# ETH1G_RGMII_RTL8211F.net
KiCad netlist of a schematic drawn in Altium Designer
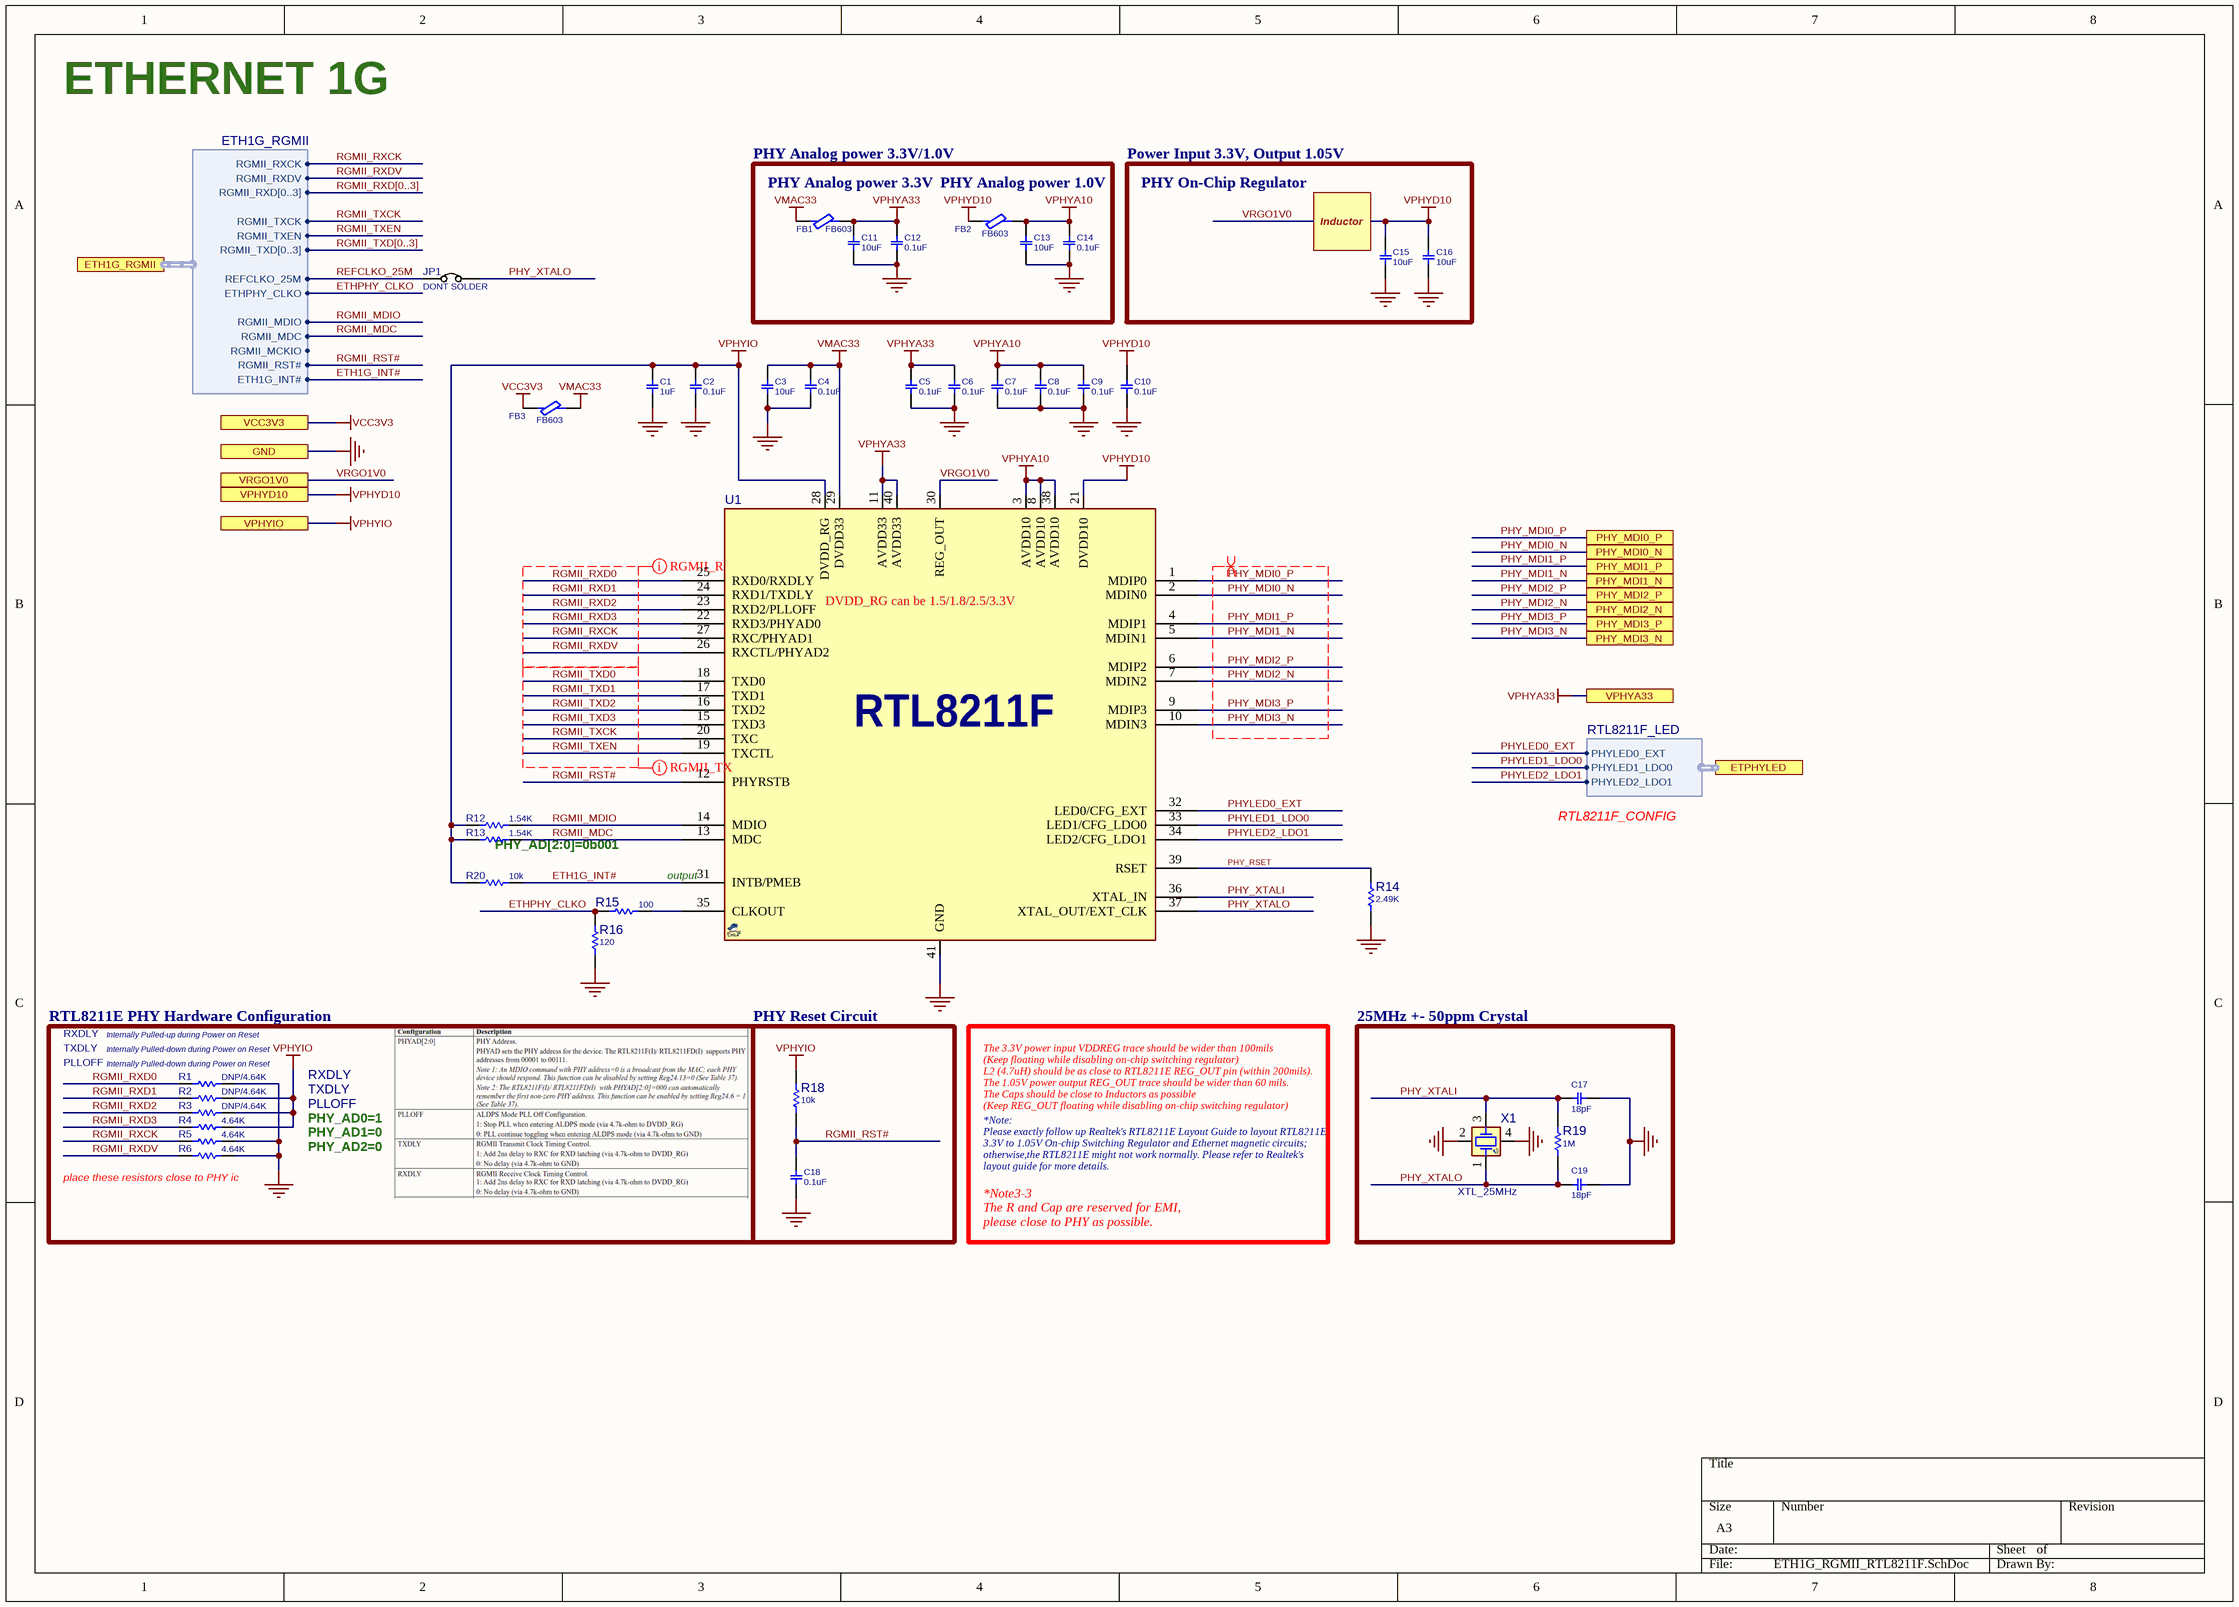
[diagram p0: ETH1G_RGMII_RTL8211F.SchDoc]

(export (version "E")
  (design (tool "Eeschema 10.0.6"))
  (components
    (comp (ref "C1")
      (value "1uF")
      (footprint "C0402")
      (description "CAP, MLCC")
      (fields (field (name "MANF_P#") "CL05A105KO5NNND") (field (name "MANF") "Samsung"))
      (libsource (lib "passive_smd") (part "CAP_SMD_MLCC"))
    )
    (comp (ref "C2")
      (value "0.1uF")
      (footprint "C0402")
      (description "CAP, MLCC")
      (fields (field (name "MANF_P#") "GRM155R61E104") (field (name "MANF") "Murata"))
      (libsource (lib "mlcc_smd_passive") (part "CAP_SMD_MLCC_100n50T"))
    )
    (comp (ref "C3")
      (value "10uF")
      (footprint "C0402")
      (description "CAP, MLCC")
      (fields (field (name "MANF_P#") "CL05A106MP5NUNC") (field (name "MANF") "Samsung"))
      (libsource (lib "mlcc_smd_passive") (part "CAP_SMD_MLCC_100n50T"))
    )
    (comp (ref "C4")
      (value "0.1uF")
      (footprint "C0402")
      (description "CAP, MLCC")
      (fields (field (name "MANF_P#") "GRM155R61E104") (field (name "MANF") "Murata"))
      (libsource (lib "mlcc_smd_passive") (part "CAP_SMD_MLCC_100n50T"))
    )
    (comp (ref "C5")
      (value "0.1uF")
      (footprint "C0402")
      (description "CAP, MLCC")
      (fields (field (name "MANF_P#") "GRM155R61E104") (field (name "MANF") "Murata"))
      (libsource (lib "mlcc_smd_passive") (part "CAP_SMD_MLCC_100n50T"))
    )
    (comp (ref "C6")
      (value "0.1uF")
      (footprint "C0402")
      (description "CAP, MLCC")
      (fields (field (name "MANF_P#") "GRM155R61E104") (field (name "MANF") "Murata"))
      (libsource (lib "mlcc_smd_passive") (part "CAP_SMD_MLCC_100n50T"))
    )
    (comp (ref "C7")
      (value "0.1uF")
      (footprint "C0402")
      (description "CAP, MLCC")
      (fields (field (name "MANF_P#") "GRM155R61E104") (field (name "MANF") "Murata"))
      (libsource (lib "mlcc_smd_passive") (part "CAP_SMD_MLCC_100n50T"))
    )
    (comp (ref "C8")
      (value "0.1uF")
      (footprint "C0402")
      (description "CAP, MLCC")
      (fields (field (name "MANF_P#") "GRM155R61E104") (field (name "MANF") "Murata"))
      (libsource (lib "mlcc_smd_passive") (part "CAP_SMD_MLCC_100n50T"))
    )
    (comp (ref "C9")
      (value "0.1uF")
      (footprint "C0402")
      (description "CAP, MLCC")
      (fields (field (name "MANF_P#") "GRM155R61E104") (field (name "MANF") "Murata"))
      (libsource (lib "mlcc_smd_passive") (part "CAP_SMD_MLCC_100n50T"))
    )
    (comp (ref "C10")
      (value "0.1uF")
      (footprint "C0402")
      (description "CAP, MLCC")
      (fields (field (name "MANF_P#") "GRM155R61E104") (field (name "MANF") "Murata"))
      (libsource (lib "mlcc_smd_passive") (part "CAP_SMD_MLCC_100n50T"))
    )
    (comp (ref "C11")
      (value "10uF")
      (footprint "C0402")
      (description "CAP, MLCC")
      (fields (field (name "MANF_P#") "CL05A106MP5NUNC") (field (name "MANF") "Samsung"))
      (libsource (lib "mlcc_smd_passive") (part "CAP_SMD_MLCC_100n50T"))
    )
    (comp (ref "C12")
      (value "0.1uF")
      (footprint "C0402")
      (description "CAP, MLCC")
      (fields (field (name "MANF_P#") "GRM155R61E104") (field (name "MANF") "Murata"))
      (libsource (lib "mlcc_smd_passive") (part "CAP_SMD_MLCC_100n50T"))
    )
    (comp (ref "C13")
      (value "10uF")
      (footprint "C0402")
      (description "CAP, MLCC")
      (fields (field (name "MANF_P#") "CL05A106MP5NUNC") (field (name "MANF") "Samsung"))
      (libsource (lib "mlcc_smd_passive") (part "CAP_SMD_MLCC_100n50T"))
    )
    (comp (ref "C14")
      (value "0.1uF")
      (footprint "C0402")
      (description "CAP, MLCC")
      (fields (field (name "MANF_P#") "GRM155R61E104") (field (name "MANF") "Murata"))
      (libsource (lib "mlcc_smd_passive") (part "CAP_SMD_MLCC_100n50T"))
    )
    (comp (ref "C15")
      (value "10uF")
      (footprint "C0402")
      (description "CAP, MLCC")
      (fields (field (name "MANF_P#") "CL05A106MP5NUNC") (field (name "MANF") "Samsung"))
      (libsource (lib "mlcc_smd_passive") (part "CAP_SMD_MLCC_100n50T"))
    )
    (comp (ref "C16")
      (value "10uF")
      (footprint "C0402")
      (description "CAP, MLCC")
      (fields (field (name "MANF_P#") "CL05A106MP5NUNC") (field (name "MANF") "Samsung"))
      (libsource (lib "mlcc_smd_passive") (part "CAP_SMD_MLCC_100n50T"))
    )
    (comp (ref "C17")
      (value "18pF")
      (footprint "C0402A")
      (description "CAP, MLCC")
      (fields (field (name "MANF_P#") "CC0402JRNPO9BN180") (field (name "MANF") "Yageo"))
      (libsource (lib "mlcc_smd_passive") (part "CAP_SMD_MLCC_100n50T"))
    )
    (comp (ref "C18")
      (value "0.1uF")
      (footprint "C0402")
      (description "CAP, MLCC")
      (fields (field (name "MANF_P#") "GRM155R61E104") (field (name "MANF") "Murata"))
      (libsource (lib "mlcc_smd_passive") (part "CAP_SMD_MLCC_100n50T"))
    )
    (comp (ref "C19")
      (value "18pF")
      (footprint "C0402A")
      (description "CAP, MLCC")
      (fields (field (name "MANF_P#") "CC0402JRNPO9BN180") (field (name "MANF") "Yageo"))
      (libsource (lib "mlcc_smd_passive") (part "CAP_SMD_MLCC_100n50T"))
    )
    (comp (ref "FB1")
      (value "FB603")
      (footprint "L0603")
      (description "FERRITE_Bead, 0603, 0.8A, 300mOhm, 1000@100MHz")
      (fields (field (name "MANF") "MURATA") (field (name "MANF_P#") "BLM18KG601SN1D"))
      (libsource (lib "emi_filter") (part "FBEAD_SMD_MPZ1608S102"))
    )
    (comp (ref "FB2")
      (value "FB603")
      (footprint "L0603")
      (description "FERRITE_Bead, 0603, 0.8A, 300mOhm, 1000@100MHz")
      (fields (field (name "MANF") "MURATA") (field (name "MANF_P#") "BLM18KG601SN1D"))
      (libsource (lib "emi_filter") (part "FBEAD_SMD_MPZ1608S102"))
    )
    (comp (ref "FB3")
      (value "FB603")
      (footprint "L0603")
      (description "FERRITE_Bead, 0603, 0.8A, 300mOhm, 1000@100MHz")
      (fields (field (name "MANF") "MURATA") (field (name "MANF_P#") "BLM18KG601SN1D"))
      (libsource (lib "emi_filter") (part "FBEAD_SMD_MPZ1608S102"))
    )
    (comp (ref "JP1")
      (value "DONT SOLDER")
      (footprint "JP_40X50")
      (description "JUMPER,  solder")
      (fields (field (name "MANF") "MANF") (field (name "MANF_P#") "MANF_P#"))
      (libsource (lib "test-tp_jumper") (part "JUMPER_SOLDER"))
    )
    (comp (ref "R1")
      (value "DNP/4.64K")
      (footprint "R0402")
      (description "RESISTOR, SMD")
      (libsource (lib "passive_res_smd") (part "RES_SMD_10K_0402"))
    )
    (comp (ref "R2")
      (value "DNP/4.64K")
      (footprint "R0402")
      (description "RESISTOR, SMD")
      (libsource (lib "passive_res_smd") (part "RES_SMD_10K_0402"))
    )
    (comp (ref "R3")
      (value "DNP/4.64K")
      (footprint "R0402")
      (description "RESISTOR, SMD")
      (libsource (lib "passive_res_smd") (part "RES_SMD_10K_0402"))
    )
    (comp (ref "R4")
      (value "4.64K")
      (footprint "R0402")
      (description "RESISTOR, SMD")
      (libsource (lib "passive_res_smd") (part "RES_SMD_10K_0402"))
    )
    (comp (ref "R5")
      (value "4.64K")
      (footprint "R0402")
      (description "RESISTOR, SMD")
      (libsource (lib "passive_res_smd") (part "RES_SMD_10K_0402"))
    )
    (comp (ref "R6")
      (value "4.64K")
      (footprint "R0402")
      (description "RESISTOR, SMD")
      (libsource (lib "passive_res_smd") (part "RES_SMD_10K_0402"))
    )
    (comp (ref "R12")
      (value "1.54K")
      (footprint "R0402")
      (description "RESISTOR, SMD")
      (libsource (lib "passive_res_smd") (part "RES_SMD_10K_0402"))
    )
    (comp (ref "R13")
      (value "1.54K")
      (footprint "R0402")
      (description "RESISTOR, SMD")
      (libsource (lib "passive_res_smd") (part "RES_SMD_10K_0402"))
    )
    (comp (ref "R14")
      (value "2.49K")
      (footprint "R0402")
      (description "RESISTOR, SMD")
      (libsource (lib "passive_res_smd") (part "RES_SMD_10K_0402"))
    )
    (comp (ref "R15")
      (value "100")
      (footprint "R0402")
      (description "RESISTOR, SMD")
      (libsource (lib "passive_res_smd") (part "RES_SMD_10K_0402"))
    )
    (comp (ref "R16")
      (value "120")
      (footprint "R0402")
      (description "RESISTOR, SMD")
      (libsource (lib "passive_res_smd") (part "RES_SMD_10K_0402"))
    )
    (comp (ref "R18")
      (value "10k")
      (footprint "R0402")
      (description "RESISTOR, SMD")
      (libsource (lib "passive_res_smd") (part "RES_SMD_10K_0402"))
    )
    (comp (ref "R19")
      (value "1M")
      (footprint "R0402")
      (description "RESISTOR, SMD")
      (libsource (lib "passive_res_smd") (part "RES_SMD_10K_0402"))
    )
    (comp (ref "R20")
      (value "10k")
      (footprint "R0402")
      (description "RESISTOR, SMD")
      (libsource (lib "passive_res_smd") (part "RES_SMD_10K_0402"))
    )
    (comp (ref "U1")
      (value "RTL8211F")
      (footprint "QFN40_40T")
      (description "Ethernet Transceiver, 10/100/1000, RGMII")
      (fields (field (name "MANF_P#") "RTL8211FI-CG") (field (name "MANF") "Realtek"))
      (libsource (lib "ethernet") (part "RTL8211F_QFN40"))
    )
    (comp (ref "X1")
      (value "XTL_25MHz")
      (footprint "XTL_4_2016")
      (description "CRYSTAL 25.00 MHZ 6pF, 10PPM")
      (fields (field (name "MANF") "Murata") (field (name "MANF_P#") "XRCGB25M000F1H00R0"))
      (libsource (lib "crystal") (part "XTL_4_25MHz_3225"))
    )
  )
  (nets
    (net (code "3") (name "/ETH1G_INT#") (class "Default")
      (node (ref "R20") (pin "2") (pinfunction "2_2") (pintype "passive"))
      (node (ref "U1") (pin "31") (pinfunction "INTB/PMEB_31") (pintype "passive"))
    )
    (net (code "5") (name "/ETHPHY_CLKO") (class "Default")
      (node (ref "R15") (pin "1") (pinfunction "1_1") (pintype "passive"))
      (node (ref "R16") (pin "2") (pinfunction "2_2") (pintype "passive"))
    )
    (net (code "6") (name "/PHYLED0_EXT") (class "Default")
      (node (ref "U1") (pin "32") (pinfunction "LED0/CFG_EXT_32") (pintype "passive"))
    )
    (net (code "7") (name "/PHYLED1_LDO0") (class "Default")
      (node (ref "U1") (pin "33") (pinfunction "LED1/CFG_LDO0_33") (pintype "passive"))
    )
    (net (code "8") (name "/PHYLED2_LDO1") (class "Default")
      (node (ref "U1") (pin "34") (pinfunction "LED2/CFG_LDO1_34") (pintype "passive"))
    )
    (net (code "9") (name "/PHY_MDI0_N") (class "Default")
      (node (ref "U1") (pin "2") (pinfunction "MDIN0_2") (pintype "passive"))
    )
    (net (code "10") (name "/PHY_MDI0_P") (class "Default")
      (node (ref "U1") (pin "1") (pinfunction "MDIP0_1") (pintype "passive"))
    )
    (net (code "11") (name "/PHY_MDI1_N") (class "Default")
      (node (ref "U1") (pin "5") (pinfunction "MDIN1_5") (pintype "passive"))
    )
    (net (code "12") (name "/PHY_MDI1_P") (class "Default")
      (node (ref "U1") (pin "4") (pinfunction "MDIP1_4") (pintype "passive"))
    )
    (net (code "13") (name "/PHY_MDI2_N") (class "Default")
      (node (ref "U1") (pin "7") (pinfunction "MDIN2_7") (pintype "passive"))
    )
    (net (code "14") (name "/PHY_MDI2_P") (class "Default")
      (node (ref "U1") (pin "6") (pinfunction "MDIP2_6") (pintype "passive"))
    )
    (net (code "15") (name "/PHY_MDI3_N") (class "Default")
      (node (ref "U1") (pin "10") (pinfunction "MDIN3_10") (pintype "passive"))
    )
    (net (code "16") (name "/PHY_MDI3_P") (class "Default")
      (node (ref "U1") (pin "9") (pinfunction "MDIP3_9") (pintype "passive"))
    )
    (net (code "17") (name "/PHY_RSET") (class "Default")
      (node (ref "R14") (pin "2") (pinfunction "2_2") (pintype "passive"))
      (node (ref "U1") (pin "39") (pinfunction "RSET_39") (pintype "passive"))
    )
    (net (code "18") (name "/PHY_XTALI") (class "Default")
      (node (ref "C17") (pin "1") (pinfunction "1_1") (pintype "passive"))
      (node (ref "R19") (pin "2") (pinfunction "2_2") (pintype "passive"))
      (node (ref "U1") (pin "36") (pinfunction "XTAL_IN_36") (pintype "passive"))
      (node (ref "X1") (pin "3") (pinfunction "XB_3") (pintype "passive"))
    )
    (net (code "19") (name "/PHY_XTALO") (class "Default")
      (node (ref "C19") (pin "1") (pinfunction "1_1") (pintype "passive"))
      (node (ref "JP1") (pin "2") (pinfunction "2_2") (pintype "passive"))
      (node (ref "R19") (pin "1") (pinfunction "1_1") (pintype "passive"))
      (node (ref "U1") (pin "37") (pinfunction "XTAL_OUT/EXT_CLK_37") (pintype "passive"))
      (node (ref "X1") (pin "1") (pinfunction "XA_1") (pintype "passive"))
    )
    (net (code "20") (name "/REFCLKO_25M") (class "Default")
      (node (ref "JP1") (pin "1") (pinfunction "1_1") (pintype "passive"))
    )
    (net (code "21") (name "/RGMII_MDC") (class "Default")
      (node (ref "R13") (pin "2") (pinfunction "2_2") (pintype "passive"))
      (node (ref "U1") (pin "13") (pinfunction "MDC_13") (pintype "passive"))
    )
    (net (code "22") (name "/RGMII_MDIO") (class "Default")
      (node (ref "R12") (pin "2") (pinfunction "2_2") (pintype "passive"))
      (node (ref "U1") (pin "14") (pinfunction "MDIO_14") (pintype "passive"))
    )
    (net (code "23") (name "/RGMII_RST#") (class "Default")
      (node (ref "C18") (pin "2") (pinfunction "2_2") (pintype "passive"))
      (node (ref "R18") (pin "2") (pinfunction "2_2") (pintype "passive"))
      (node (ref "U1") (pin "12") (pinfunction "PHYRSTB_12") (pintype "passive"))
    )
    (net (code "24") (name "/RGMII_RXCK") (class "Default")
      (node (ref "R5") (pin "1") (pinfunction "1_1") (pintype "passive"))
      (node (ref "U1") (pin "27") (pinfunction "RXC/PHYAD1_27") (pintype "passive"))
    )
    (net (code "25") (name "/RGMII_RXD0") (class "Default")
      (node (ref "R1") (pin "1") (pinfunction "1_1") (pintype "passive"))
      (node (ref "U1") (pin "25") (pinfunction "RXD0/RXDLY_25") (pintype "passive"))
    )
    (net (code "26") (name "/RGMII_RXD1") (class "Default")
      (node (ref "R2") (pin "1") (pinfunction "1_1") (pintype "passive"))
      (node (ref "U1") (pin "24") (pinfunction "RXD1/TXDLY_24") (pintype "passive"))
    )
    (net (code "27") (name "/RGMII_RXD2") (class "Default")
      (node (ref "R3") (pin "1") (pinfunction "1_1") (pintype "passive"))
      (node (ref "U1") (pin "23") (pinfunction "RXD2/PLLOFF_23") (pintype "passive"))
    )
    (net (code "28") (name "/RGMII_RXD3") (class "Default")
      (node (ref "R4") (pin "1") (pinfunction "1_1") (pintype "passive"))
      (node (ref "U1") (pin "22") (pinfunction "RXD3/PHYAD0_22") (pintype "passive"))
    )
    (net (code "29") (name "/RGMII_RXDV") (class "Default")
      (node (ref "R6") (pin "1") (pinfunction "1_1") (pintype "passive"))
      (node (ref "U1") (pin "26") (pinfunction "RXCTL/PHYAD2_26") (pintype "passive"))
    )
    (net (code "30") (name "/RGMII_TXCK") (class "Default")
      (node (ref "U1") (pin "20") (pinfunction "TXC_20") (pintype "passive"))
    )
    (net (code "31") (name "/RGMII_TXD0") (class "Default")
      (node (ref "U1") (pin "18") (pinfunction "TXD0_18") (pintype "passive"))
    )
    (net (code "32") (name "/RGMII_TXD1") (class "Default")
      (node (ref "U1") (pin "17") (pinfunction "TXD1_17") (pintype "passive"))
    )
    (net (code "33") (name "/RGMII_TXD2") (class "Default")
      (node (ref "U1") (pin "16") (pinfunction "TXD2_16") (pintype "passive"))
    )
    (net (code "34") (name "/RGMII_TXD3") (class "Default")
      (node (ref "U1") (pin "15") (pinfunction "TXD3_15") (pintype "passive"))
    )
    (net (code "36") (name "/RGMII_TXEN") (class "Default")
      (node (ref "U1") (pin "19") (pinfunction "TXCTL_19") (pintype "passive"))
    )
    (net (code "37") (name "/VRGO1V0") (class "Default")
      (node (ref "U1") (pin "30") (pinfunction "REG_OUT_30") (pintype "passive"))
    )
    (net (code "40") (name "GND") (class "Default")
      (node (ref "C1") (pin "1") (pinfunction "1_1") (pintype "passive"))
      (node (ref "C10") (pin "2") (pinfunction "2_2") (pintype "passive"))
      (node (ref "C11") (pin "2") (pinfunction "2_2") (pintype "passive"))
      (node (ref "C12") (pin "2") (pinfunction "2_2") (pintype "passive"))
      (node (ref "C13") (pin "2") (pinfunction "2_2") (pintype "passive"))
      (node (ref "C14") (pin "2") (pinfunction "2_2") (pintype "passive"))
      (node (ref "C15") (pin "2") (pinfunction "2_2") (pintype "passive"))
      (node (ref "C16") (pin "2") (pinfunction "2_2") (pintype "passive"))
      (node (ref "C17") (pin "2") (pinfunction "2_2") (pintype "passive"))
      (node (ref "C18") (pin "1") (pinfunction "1_1") (pintype "passive"))
      (node (ref "C19") (pin "2") (pinfunction "2_2") (pintype "passive"))
      (node (ref "C2") (pin "2") (pinfunction "2_2") (pintype "passive"))
      (node (ref "C3") (pin "2") (pinfunction "2_2") (pintype "passive"))
      (node (ref "C4") (pin "2") (pinfunction "2_2") (pintype "passive"))
      (node (ref "C5") (pin "2") (pinfunction "2_2") (pintype "passive"))
      (node (ref "C6") (pin "2") (pinfunction "2_2") (pintype "passive"))
      (node (ref "C7") (pin "2") (pinfunction "2_2") (pintype "passive"))
      (node (ref "C8") (pin "2") (pinfunction "2_2") (pintype "passive"))
      (node (ref "C9") (pin "2") (pinfunction "2_2") (pintype "passive"))
      (node (ref "R1") (pin "2") (pinfunction "2_2") (pintype "passive"))
      (node (ref "R14") (pin "1") (pinfunction "1_1") (pintype "passive"))
      (node (ref "R16") (pin "1") (pinfunction "1_1") (pintype "passive"))
      (node (ref "R5") (pin "2") (pinfunction "2_2") (pintype "passive"))
      (node (ref "R6") (pin "2") (pinfunction "2_2") (pintype "passive"))
      (node (ref "U1") (pin "41") (pinfunction "GND_41") (pintype "passive"))
      (node (ref "X1") (pin "2") (pinfunction "GND1_2") (pintype "passive"))
      (node (ref "X1") (pin "4") (pinfunction "GND2_4") (pintype "passive"))
    )
    (net (code "41") (name "Net-(U1-CLKOUT)") (class "Default")
      (node (ref "R15") (pin "2") (pinfunction "2_2") (pintype "passive"))
      (node (ref "U1") (pin "35") (pinfunction "CLKOUT_35") (pintype "passive"))
    )
    (net (code "42") (name "VCC3V3") (class "Default")
      (node (ref "FB3") (pin "1") (pinfunction "1_1") (pintype "passive"))
    )
    (net (code "43") (name "VMAC33") (class "Default")
      (node (ref "C3") (pin "1") (pinfunction "1_1") (pintype "passive"))
      (node (ref "C4") (pin "1") (pinfunction "1_1") (pintype "passive"))
      (node (ref "FB1") (pin "1") (pinfunction "1_1") (pintype "passive"))
      (node (ref "FB3") (pin "2") (pinfunction "2_2") (pintype "passive"))
      (node (ref "U1") (pin "29") (pinfunction "DVDD33_29") (pintype "passive"))
    )
    (net (code "44") (name "VPHYA10") (class "Default")
      (node (ref "C13") (pin "1") (pinfunction "1_1") (pintype "passive"))
      (node (ref "C14") (pin "1") (pinfunction "1_1") (pintype "passive"))
      (node (ref "C7") (pin "1") (pinfunction "1_1") (pintype "passive"))
      (node (ref "C8") (pin "1") (pinfunction "1_1") (pintype "passive"))
      (node (ref "C9") (pin "1") (pinfunction "1_1") (pintype "passive"))
      (node (ref "FB2") (pin "2") (pinfunction "2_2") (pintype "passive"))
      (node (ref "U1") (pin "3") (pinfunction "AVDD10_3") (pintype "passive"))
      (node (ref "U1") (pin "38") (pinfunction "AVDD10_38") (pintype "passive"))
      (node (ref "U1") (pin "8") (pinfunction "AVDD10_8") (pintype "passive"))
    )
    (net (code "45") (name "VPHYA33") (class "Default")
      (node (ref "C11") (pin "1") (pinfunction "1_1") (pintype "passive"))
      (node (ref "C12") (pin "1") (pinfunction "1_1") (pintype "passive"))
      (node (ref "C5") (pin "1") (pinfunction "1_1") (pintype "passive"))
      (node (ref "C6") (pin "1") (pinfunction "1_1") (pintype "passive"))
      (node (ref "FB1") (pin "2") (pinfunction "2_2") (pintype "passive"))
      (node (ref "U1") (pin "11") (pinfunction "AVDD33_11") (pintype "passive"))
      (node (ref "U1") (pin "40") (pinfunction "AVDD33_40") (pintype "passive"))
    )
    (net (code "46") (name "VPHYD10") (class "Default")
      (node (ref "C10") (pin "1") (pinfunction "1_1") (pintype "passive"))
      (node (ref "C15") (pin "1") (pinfunction "1_1") (pintype "passive"))
      (node (ref "C16") (pin "1") (pinfunction "1_1") (pintype "passive"))
      (node (ref "FB2") (pin "1") (pinfunction "1_1") (pintype "passive"))
      (node (ref "U1") (pin "21") (pinfunction "DVDD10_21") (pintype "passive"))
    )
    (net (code "47") (name "VPHYIO") (class "Default")
      (node (ref "C1") (pin "2") (pinfunction "2_2") (pintype "passive"))
      (node (ref "C2") (pin "1") (pinfunction "1_1") (pintype "passive"))
      (node (ref "R12") (pin "1") (pinfunction "1_1") (pintype "passive"))
      (node (ref "R13") (pin "1") (pinfunction "1_1") (pintype "passive"))
      (node (ref "R18") (pin "1") (pinfunction "1_1") (pintype "passive"))
      (node (ref "R2") (pin "2") (pinfunction "2_2") (pintype "passive"))
      (node (ref "R20") (pin "1") (pinfunction "1_1") (pintype "passive"))
      (node (ref "R3") (pin "2") (pinfunction "2_2") (pintype "passive"))
      (node (ref "R4") (pin "2") (pinfunction "2_2") (pintype "passive"))
      (node (ref "U1") (pin "28") (pinfunction "DVDD_RG_28") (pintype "passive"))
    )
  )
)
